# Phase_Voltages.net
KiCad netlist of a schematic drawn in Altium Designer
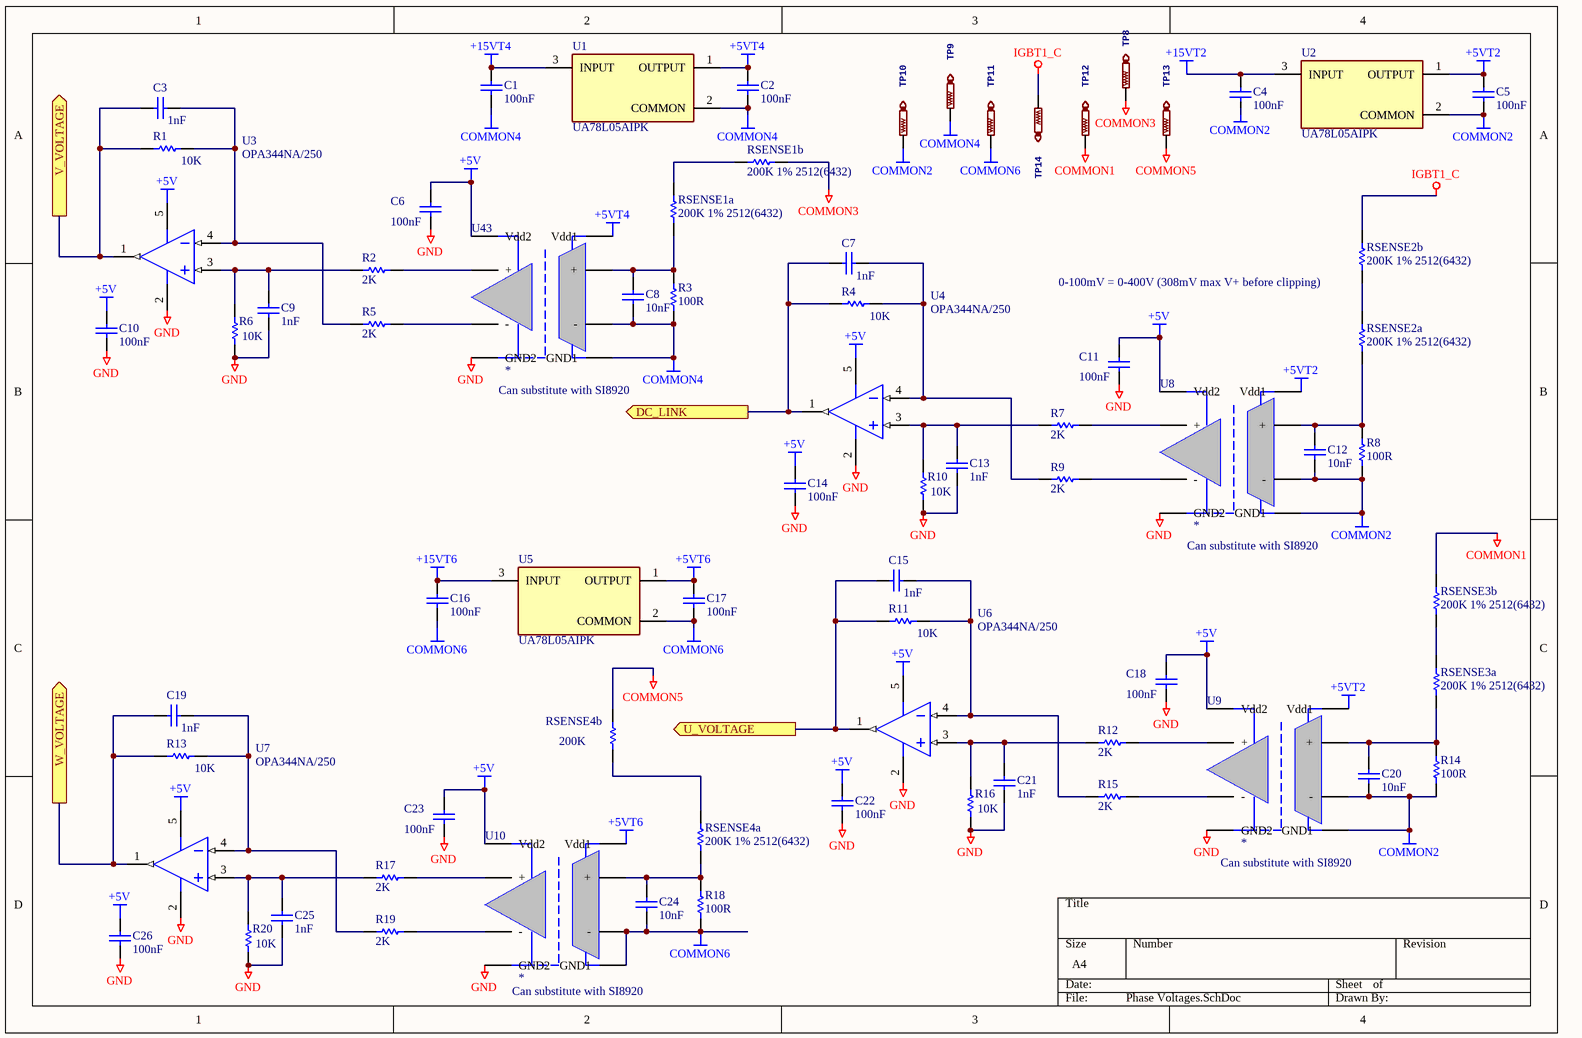
[diagram p0: Phase Voltages.SchDoc]

(export (version "E")
  (design (tool "Eeschema 10.0.6"))
  (components
    (comp (ref "C1")
      (value "100nF")
      (footprint "CAPC0805(2012)75_N")
      (description "CAP 100nF 25V -20% to +80% 0805 (2012 Metric) Thickness 0.75mm SMD")
      (fields (field (name "TOLERANCE") "-20% to +80%") (field (name "Comment") "CAP 100nF 25V 0805(2012)"))
      (libsource (lib "Altium Content Vault") (part "CMP-1036-04415-1"))
    )
    (comp (ref "C2")
      (value "100nF")
      (footprint "CAPC0805(2012)75_N")
      (description "CAP 100nF 25V -20% to +80% 0805 (2012 Metric) Thickness 0.75mm SMD")
      (fields (field (name "TOLERANCE") "-20% to +80%") (field (name "Comment") "CAP 100nF 25V 0805(2012)"))
      (libsource (lib "Altium Content Vault") (part "CMP-1036-04415-1"))
    )
    (comp (ref "C3")
      (value "1nF")
      (footprint "CAPC0805(2012)145_L")
      (description "CAP 1nF 16V ±5% 0805 (2012 Metric) Thickness 1.45mm SMD")
      (fields (field (name "TOLERANCE") "Â±5%") (field (name "Comment") "CAP 1nF 16V 0805(2012)"))
      (libsource (lib "Altium Content Vault") (part "CMP-1036-02957-1"))
    )
    (comp (ref "C4")
      (value "100nF")
      (footprint "CAPC0805(2012)75_N")
      (description "CAP 100nF 25V -20% to +80% 0805 (2012 Metric) Thickness 0.75mm SMD")
      (fields (field (name "TOLERANCE") "-20% to +80%") (field (name "Comment") "CAP 100nF 25V 0805(2012)"))
      (libsource (lib "Altium Content Vault") (part "CMP-1036-04415-1"))
    )
    (comp (ref "C5")
      (value "100nF")
      (footprint "CAPC0805(2012)75_N")
      (description "CAP 100nF 25V -20% to +80% 0805 (2012 Metric) Thickness 0.75mm SMD")
      (fields (field (name "TOLERANCE") "-20% to +80%") (field (name "Comment") "CAP 100nF 25V 0805(2012)"))
      (libsource (lib "Altium Content Vault") (part "CMP-1036-04415-1"))
    )
    (comp (ref "C6")
      (value "100nF")
      (footprint "CAPC0805(2012)75_N")
      (description "CAP 100nF 25V -20% to +80% 0805 (2012 Metric) Thickness 0.75mm SMD")
      (fields (field (name "TOLERANCE") "-20% to +80%") (field (name "Comment") "CAP 100nF 25V 0805(2012)"))
      (libsource (lib "Altium Content Vault") (part "CMP-1036-04415-1"))
    )
    (comp (ref "C7")
      (value "1nF")
      (footprint "CAPC0805(2012)145_L")
      (description "CAP 1nF 16V ±5% 0805 (2012 Metric) Thickness 1.45mm SMD")
      (fields (field (name "TOLERANCE") "Â±5%") (field (name "Comment") "CAP 1nF 16V 0805(2012)"))
      (libsource (lib "Altium Content Vault") (part "CMP-1036-02957-1"))
    )
    (comp (ref "C8")
      (value "10nF")
      (footprint "CAPC0805(2012)100_L")
      (description "CAP 10nF 25V ±5% 0805 (2012 Metric) Thickness 1mm SMD")
      (fields (field (name "TOLERANCE") "Â±5%") (field (name "Comment") "CAP 10nF 25V 0805(2012)"))
      (libsource (lib "Altium Content Vault") (part "CMP-1036-03829-1"))
    )
    (comp (ref "C9")
      (value "1nF")
      (footprint "CAPC0805(2012)145_L")
      (description "CAP 1nF 16V ±5% 0805 (2012 Metric) Thickness 1.45mm SMD")
      (fields (field (name "TOLERANCE") "Â±5%") (field (name "Comment") "CAP 1nF 16V 0805(2012)"))
      (libsource (lib "Altium Content Vault") (part "CMP-1036-02957-1"))
    )
    (comp (ref "C10")
      (value "100nF")
      (footprint "CAPC0805(2012)75_N")
      (description "CAP 100nF 25V -20% to +80% 0805 (2012 Metric) Thickness 0.75mm SMD")
      (fields (field (name "TOLERANCE") "-20% to +80%") (field (name "Comment") "CAP 100nF 25V 0805(2012)"))
      (libsource (lib "Altium Content Vault") (part "CMP-1036-04415-1"))
    )
    (comp (ref "C11")
      (value "100nF")
      (footprint "CAPC0805(2012)75_N")
      (description "CAP 100nF 25V -20% to +80% 0805 (2012 Metric) Thickness 0.75mm SMD")
      (fields (field (name "TOLERANCE") "-20% to +80%") (field (name "Comment") "CAP 100nF 25V 0805(2012)"))
      (libsource (lib "Altium Content Vault") (part "CMP-1036-04415-1"))
    )
    (comp (ref "C12")
      (value "10nF")
      (footprint "CAPC0805(2012)100_L")
      (description "CAP 10nF 25V ±5% 0805 (2012 Metric) Thickness 1mm SMD")
      (fields (field (name "TOLERANCE") "Â±5%") (field (name "Comment") "CAP 10nF 25V 0805(2012)"))
      (libsource (lib "Altium Content Vault") (part "CMP-1036-03829-1"))
    )
    (comp (ref "C13")
      (value "1nF")
      (footprint "CAPC0805(2012)145_L")
      (description "CAP 1nF 16V ±5% 0805 (2012 Metric) Thickness 1.45mm SMD")
      (fields (field (name "TOLERANCE") "Â±5%") (field (name "Comment") "CAP 1nF 16V 0805(2012)"))
      (libsource (lib "Altium Content Vault") (part "CMP-1036-02957-1"))
    )
    (comp (ref "C14")
      (value "100nF")
      (footprint "CAPC0805(2012)75_N")
      (description "CAP 100nF 25V -20% to +80% 0805 (2012 Metric) Thickness 0.75mm SMD")
      (fields (field (name "TOLERANCE") "-20% to +80%") (field (name "Comment") "CAP 100nF 25V 0805(2012)"))
      (libsource (lib "Altium Content Vault") (part "CMP-1036-04415-1"))
    )
    (comp (ref "C15")
      (value "1nF")
      (footprint "CAPC0805(2012)145_L")
      (description "CAP 1nF 16V ±5% 0805 (2012 Metric) Thickness 1.45mm SMD")
      (fields (field (name "TOLERANCE") "Â±5%") (field (name "Comment") "CAP 1nF 16V 0805(2012)"))
      (libsource (lib "Altium Content Vault") (part "CMP-1036-02957-1"))
    )
    (comp (ref "C16")
      (value "100nF")
      (footprint "CAPC0805(2012)75_N")
      (description "CAP 100nF 25V -20% to +80% 0805 (2012 Metric) Thickness 0.75mm SMD")
      (fields (field (name "TOLERANCE") "-20% to +80%") (field (name "Comment") "CAP 100nF 25V 0805(2012)"))
      (libsource (lib "Altium Content Vault") (part "CMP-1036-04415-1"))
    )
    (comp (ref "C17")
      (value "100nF")
      (footprint "CAPC0805(2012)75_N")
      (description "CAP 100nF 25V -20% to +80% 0805 (2012 Metric) Thickness 0.75mm SMD")
      (fields (field (name "TOLERANCE") "-20% to +80%") (field (name "Comment") "CAP 100nF 25V 0805(2012)"))
      (libsource (lib "Altium Content Vault") (part "CMP-1036-04415-1"))
    )
    (comp (ref "C18")
      (value "100nF")
      (footprint "CAPC0805(2012)75_N")
      (description "CAP 100nF 25V -20% to +80% 0805 (2012 Metric) Thickness 0.75mm SMD")
      (fields (field (name "TOLERANCE") "-20% to +80%") (field (name "Comment") "CAP 100nF 25V 0805(2012)"))
      (libsource (lib "Altium Content Vault") (part "CMP-1036-04415-1"))
    )
    (comp (ref "C19")
      (value "1nF")
      (footprint "CAPC0805(2012)145_L")
      (description "CAP 1nF 16V ±5% 0805 (2012 Metric) Thickness 1.45mm SMD")
      (fields (field (name "TOLERANCE") "Â±5%") (field (name "Comment") "CAP 1nF 16V 0805(2012)"))
      (libsource (lib "Altium Content Vault") (part "CMP-1036-02957-1"))
    )
    (comp (ref "C20")
      (value "10nF")
      (footprint "CAPC0805(2012)100_L")
      (description "CAP 10nF 25V ±5% 0805 (2012 Metric) Thickness 1mm SMD")
      (fields (field (name "TOLERANCE") "Â±5%") (field (name "Comment") "CAP 10nF 25V 0805(2012)"))
      (libsource (lib "Altium Content Vault") (part "CMP-1036-03829-1"))
    )
    (comp (ref "C21")
      (value "1nF")
      (footprint "CAPC0805(2012)145_L")
      (description "CAP 1nF 16V ±5% 0805 (2012 Metric) Thickness 1.45mm SMD")
      (fields (field (name "TOLERANCE") "Â±5%") (field (name "Comment") "CAP 1nF 16V 0805(2012)"))
      (libsource (lib "Altium Content Vault") (part "CMP-1036-02957-1"))
    )
    (comp (ref "C22")
      (value "100nF")
      (footprint "CAPC0805(2012)75_N")
      (description "CAP 100nF 25V -20% to +80% 0805 (2012 Metric) Thickness 0.75mm SMD")
      (fields (field (name "TOLERANCE") "-20% to +80%") (field (name "Comment") "CAP 100nF 25V 0805(2012)"))
      (libsource (lib "Altium Content Vault") (part "CMP-1036-04415-1"))
    )
    (comp (ref "C23")
      (value "100nF")
      (footprint "CAPC0805(2012)75_N")
      (description "CAP 100nF 25V -20% to +80% 0805 (2012 Metric) Thickness 0.75mm SMD")
      (fields (field (name "TOLERANCE") "-20% to +80%") (field (name "Comment") "CAP 100nF 25V 0805(2012)"))
      (libsource (lib "Altium Content Vault") (part "CMP-1036-04415-1"))
    )
    (comp (ref "C24")
      (value "10nF")
      (footprint "CAPC0805(2012)100_L")
      (description "CAP 10nF 25V ±5% 0805 (2012 Metric) Thickness 1mm SMD")
      (fields (field (name "TOLERANCE") "Â±5%") (field (name "Comment") "CAP 10nF 25V 0805(2012)"))
      (libsource (lib "Altium Content Vault") (part "CMP-1036-03829-1"))
    )
    (comp (ref "C25")
      (value "1nF")
      (footprint "CAPC0805(2012)145_L")
      (description "CAP 1nF 16V ±5% 0805 (2012 Metric) Thickness 1.45mm SMD")
      (fields (field (name "TOLERANCE") "Â±5%") (field (name "Comment") "CAP 1nF 16V 0805(2012)"))
      (libsource (lib "Altium Content Vault") (part "CMP-1036-02957-1"))
    )
    (comp (ref "C26")
      (value "100nF")
      (footprint "CAPC0805(2012)75_N")
      (description "CAP 100nF 25V -20% to +80% 0805 (2012 Metric) Thickness 0.75mm SMD")
      (fields (field (name "TOLERANCE") "-20% to +80%") (field (name "Comment") "CAP 100nF 25V 0805(2012)"))
      (libsource (lib "Altium Content Vault") (part "CMP-1036-04415-1"))
    )
    (comp (ref "R1")
      (value "10K")
      (footprint "RESC0805(2012)_M")
      (description "10K 0.125W 1% 0805 (2012 Metric)  SMD")
      (fields (field (name "TOLERANCE") "1 %") (field (name "POWER") "0.125 W"))
      (libsource (lib "Altium Content Vault") (part "CMP-1013-00623-1"))
    )
    (comp (ref "R2")
      (value "2K")
      (footprint "RESC0805(2012)_L")
      (description "2K 0.125W 1% 0805 (2012 Metric)  SMD")
      (fields (field (name "POWER") "0.125 W") (field (name "TOLERANCE") "1 %"))
      (libsource (lib "Altium Content Vault") (part "CMP-1013-00542-1"))
    )
    (comp (ref "R3")
      (value "100R")
      (footprint "RESC0805(2012)_L")
      (description "100R 0.125W 1% 0805 (2012 Metric)  SMD")
      (fields (field (name "POWER") "0.125 W") (field (name "TOLERANCE") "1 %"))
      (libsource (lib "Altium Content Vault") (part "CMP-1013-00397-1"))
    )
    (comp (ref "R4")
      (value "10K")
      (footprint "RESC0805(2012)_M")
      (description "10K 0.125W 1% 0805 (2012 Metric)  SMD")
      (fields (field (name "TOLERANCE") "1 %") (field (name "POWER") "0.125 W"))
      (libsource (lib "Altium Content Vault") (part "CMP-1013-00623-1"))
    )
    (comp (ref "R5")
      (value "2K")
      (footprint "RESC0805(2012)_L")
      (description "2K 0.125W 1% 0805 (2012 Metric)  SMD")
      (fields (field (name "POWER") "0.125 W") (field (name "TOLERANCE") "1 %"))
      (libsource (lib "Altium Content Vault") (part "CMP-1013-00542-1"))
    )
    (comp (ref "R6")
      (value "10K")
      (footprint "RESC0805(2012)_M")
      (description "10K 0.125W 1% 0805 (2012 Metric)  SMD")
      (fields (field (name "TOLERANCE") "1 %") (field (name "POWER") "0.125 W"))
      (libsource (lib "Altium Content Vault") (part "CMP-1013-00623-1"))
    )
    (comp (ref "R7")
      (value "2K")
      (footprint "RESC0805(2012)_L")
      (description "2K 0.125W 1% 0805 (2012 Metric)  SMD")
      (fields (field (name "POWER") "0.125 W") (field (name "TOLERANCE") "1 %"))
      (libsource (lib "Altium Content Vault") (part "CMP-1013-00542-1"))
    )
    (comp (ref "R8")
      (value "100R")
      (footprint "RESC0805(2012)_L")
      (description "100R 0.125W 1% 0805 (2012 Metric)  SMD")
      (fields (field (name "POWER") "0.125 W") (field (name "TOLERANCE") "1 %"))
      (libsource (lib "Altium Content Vault") (part "CMP-1013-00397-1"))
    )
    (comp (ref "R9")
      (value "2K")
      (footprint "RESC0805(2012)_L")
      (description "2K 0.125W 1% 0805 (2012 Metric)  SMD")
      (fields (field (name "POWER") "0.125 W") (field (name "TOLERANCE") "1 %"))
      (libsource (lib "Altium Content Vault") (part "CMP-1013-00542-1"))
    )
    (comp (ref "R10")
      (value "10K")
      (footprint "RESC0805(2012)_M")
      (description "10K 0.125W 1% 0805 (2012 Metric)  SMD")
      (fields (field (name "TOLERANCE") "1 %") (field (name "POWER") "0.125 W"))
      (libsource (lib "Altium Content Vault") (part "CMP-1013-00623-1"))
    )
    (comp (ref "R11")
      (value "10K")
      (footprint "RESC0805(2012)_M")
      (description "10K 0.125W 1% 0805 (2012 Metric)  SMD")
      (fields (field (name "TOLERANCE") "1 %") (field (name "POWER") "0.125 W"))
      (libsource (lib "Altium Content Vault") (part "CMP-1013-00623-1"))
    )
    (comp (ref "R12")
      (value "2K")
      (footprint "RESC0805(2012)_L")
      (description "2K 0.125W 1% 0805 (2012 Metric)  SMD")
      (fields (field (name "POWER") "0.125 W") (field (name "TOLERANCE") "1 %"))
      (libsource (lib "Altium Content Vault") (part "CMP-1013-00542-1"))
    )
    (comp (ref "R13")
      (value "10K")
      (footprint "RESC0805(2012)_M")
      (description "10K 0.125W 1% 0805 (2012 Metric)  SMD")
      (fields (field (name "TOLERANCE") "1 %") (field (name "POWER") "0.125 W"))
      (libsource (lib "Altium Content Vault") (part "CMP-1013-00623-1"))
    )
    (comp (ref "R14")
      (value "100R")
      (footprint "RESC0805(2012)_L")
      (description "100R 0.125W 1% 0805 (2012 Metric)  SMD")
      (fields (field (name "POWER") "0.125 W") (field (name "TOLERANCE") "1 %"))
      (libsource (lib "Altium Content Vault") (part "CMP-1013-00397-1"))
    )
    (comp (ref "R15")
      (value "2K")
      (footprint "RESC0805(2012)_L")
      (description "2K 0.125W 1% 0805 (2012 Metric)  SMD")
      (fields (field (name "POWER") "0.125 W") (field (name "TOLERANCE") "1 %"))
      (libsource (lib "Altium Content Vault") (part "CMP-1013-00542-1"))
    )
    (comp (ref "R16")
      (value "10K")
      (footprint "RESC0805(2012)_M")
      (description "10K 0.125W 1% 0805 (2012 Metric)  SMD")
      (fields (field (name "TOLERANCE") "1 %") (field (name "POWER") "0.125 W"))
      (libsource (lib "Altium Content Vault") (part "CMP-1013-00623-1"))
    )
    (comp (ref "R17")
      (value "2K")
      (footprint "RESC0805(2012)_L")
      (description "2K 0.125W 1% 0805 (2012 Metric)  SMD")
      (fields (field (name "POWER") "0.125 W") (field (name "TOLERANCE") "1 %"))
      (libsource (lib "Altium Content Vault") (part "CMP-1013-00542-1"))
    )
    (comp (ref "R18")
      (value "100R")
      (footprint "RESC0805(2012)_L")
      (description "100R 0.125W 1% 0805 (2012 Metric)  SMD")
      (fields (field (name "POWER") "0.125 W") (field (name "TOLERANCE") "1 %"))
      (libsource (lib "Altium Content Vault") (part "CMP-1013-00397-1"))
    )
    (comp (ref "R19")
      (value "2K")
      (footprint "RESC0805(2012)_L")
      (description "2K 0.125W 1% 0805 (2012 Metric)  SMD")
      (fields (field (name "POWER") "0.125 W") (field (name "TOLERANCE") "1 %"))
      (libsource (lib "Altium Content Vault") (part "CMP-1013-00542-1"))
    )
    (comp (ref "R20")
      (value "10K")
      (footprint "RESC0805(2012)_M")
      (description "10K 0.125W 1% 0805 (2012 Metric)  SMD")
      (fields (field (name "TOLERANCE") "1 %") (field (name "POWER") "0.125 W"))
      (libsource (lib "Altium Content Vault") (part "CMP-1013-00623-1"))
    )
    (comp (ref "RSENSE1a")
      (value "200K 1% 2512(6432)")
      (footprint "RESC2512(6432)_M")
      (description "200K 1W 1% 2512 (6432 Metric)  SMD")
      (fields (field (name "TOLERANCE") "1 %") (field (name "POWER") "1 W"))
      (libsource (lib "Altium Content Vault") (part "RES"))
    )
    (comp (ref "RSENSE1b")
      (value "200K 1% 2512(6432)")
      (footprint "RESC2512(6432)_M")
      (description "200K 1W 1% 2512 (6432 Metric)  SMD")
      (fields (field (name "TOLERANCE") "1 %") (field (name "POWER") "1 W"))
      (libsource (lib "Altium Content Vault") (part "RES"))
    )
    (comp (ref "RSENSE2a")
      (value "200K 1% 2512(6432)")
      (footprint "RESC2512(6432)_M")
      (description "200K 1W 1% 2512 (6432 Metric)  SMD")
      (fields (field (name "TOLERANCE") "1 %") (field (name "POWER") "1 W"))
      (libsource (lib "Altium Content Vault") (part "RES"))
    )
    (comp (ref "RSENSE2b")
      (value "200K 1% 2512(6432)")
      (footprint "RESC2512(6432)_M")
      (description "200K 1W 1% 2512 (6432 Metric)  SMD")
      (fields (field (name "TOLERANCE") "1 %") (field (name "POWER") "1 W"))
      (libsource (lib "Altium Content Vault") (part "RES"))
    )
    (comp (ref "RSENSE3a")
      (value "200K 1% 2512(6432)")
      (footprint "RESC2512(6432)_M")
      (description "200K 1W 1% 2512 (6432 Metric)  SMD")
      (fields (field (name "TOLERANCE") "1 %") (field (name "POWER") "1 W"))
      (libsource (lib "Altium Content Vault") (part "RES"))
    )
    (comp (ref "RSENSE3b")
      (value "200K 1% 2512(6432)")
      (footprint "RESC2512(6432)_M")
      (description "200K 1W 1% 2512 (6432 Metric)  SMD")
      (fields (field (name "TOLERANCE") "1 %") (field (name "POWER") "1 W"))
      (libsource (lib "Altium Content Vault") (part "RES"))
    )
    (comp (ref "RSENSE4a")
      (value "200K 1% 2512(6432)")
      (footprint "RESC2512(6432)_M")
      (description "200K 1W 1% 2512 (6432 Metric)  SMD")
      (fields (field (name "TOLERANCE") "1 %") (field (name "POWER") "1 W"))
      (libsource (lib "Altium Content Vault") (part "CMP-1018-00768-1"))
    )
    (comp (ref "RSENSE4b")
      (value "200K")
      (footprint "RESC2512(6432)_M")
      (description "200K 1W 1% 2512 (6432 Metric)  SMD")
      (fields (field (name "TOLERANCE") "1 %") (field (name "POWER") "1 W"))
      (libsource (lib "Altium Content Vault") (part "CMP-1018-00768-1"))
    )
    (comp (ref "TP8")
      (value "PTR1PAD1-13")
      (footprint "P1-13")
      (description "TEST PIN")
      (libsource (lib "testpad") (part "PTR1PAD1-13"))
    )
    (comp (ref "TP9")
      (value "PTR1PAD1-13")
      (footprint "P1-13")
      (description "TEST PIN")
      (libsource (lib "testpad") (part "PTR1PAD1-13"))
    )
    (comp (ref "TP10")
      (value "PTR1PAD1-13")
      (footprint "P1-13")
      (description "TEST PIN")
      (libsource (lib "testpad") (part "PTR1PAD1-13"))
    )
    (comp (ref "TP11")
      (value "PTR1PAD1-13")
      (footprint "P1-13")
      (description "TEST PIN")
      (libsource (lib "testpad") (part "PTR1PAD1-13"))
    )
    (comp (ref "TP12")
      (value "PTR1PAD1-13")
      (footprint "P1-13")
      (description "TEST PIN")
      (libsource (lib "testpad") (part "PTR1PAD1-13"))
    )
    (comp (ref "TP13")
      (value "PTR1PAD1-13")
      (footprint "P1-13")
      (description "TEST PIN")
      (libsource (lib "testpad") (part "PTR1PAD1-13"))
    )
    (comp (ref "TP14")
      (value "PTR1PAD1-13")
      (footprint "P1-13")
      (description "TEST PIN")
      (libsource (lib "") (part "PTR1PAD1-13_1"))
    )
    (comp (ref "U1")
      (value "UA78L05AIPK")
      (footprint "FP-PK0003A-MFG")
      (description "IC REG LINEAR 5V 100MA SOT89-3")
      (fields
        (field (name "MANUFACTURER") "Texas Instruments")
        (field (name "OCTOPART") "https://octopart.com/ua78l05aipk-texas+instruments-525592")
      )
      (libsource (lib "Altium Content Vault") (part "58e5423477dba73b0af001d1dc47a63"))
    )
    (comp (ref "U2")
      (value "UA78L05AIPK")
      (footprint "FP-PK0003A-MFG")
      (description "IC REG LINEAR 5V 100MA SOT89-3")
      (fields
        (field (name "MANUFACTURER") "Texas Instruments")
        (field (name "OCTOPART") "https://octopart.com/ua78l05aipk-texas+instruments-525592")
      )
      (libsource (lib "Altium Content Vault") (part "58e5423477dba73b0af001d1dc47a63"))
    )
    (comp (ref "U3")
      (value "OPA344NA/250")
      (footprint "DBV0005A_L")
      (fields (field (name "MANUFACTURER") "Texas Instruments"))
      (libsource (lib "Altium Content Vault") (part "CMP-0272-00879-3"))
    )
    (comp (ref "U4")
      (value "OPA344NA/250")
      (footprint "DBV0005A_L")
      (fields (field (name "MANUFACTURER") "Texas Instruments"))
      (libsource (lib "Altium Content Vault") (part "CMP-0272-00879-3"))
    )
    (comp (ref "U5")
      (value "UA78L05AIPK")
      (footprint "FP-PK0003A-MFG")
      (description "IC REG LINEAR 5V 100MA SOT89-3")
      (fields
        (field (name "MANUFACTURER") "Texas Instruments")
        (field (name "OCTOPART") "https://octopart.com/ua78l05aipk-texas+instruments-525592")
      )
      (libsource (lib "Altium Content Vault") (part "58e5423477dba73b0af001d1dc47a63"))
    )
    (comp (ref "U6")
      (value "OPA344NA/250")
      (footprint "DBV0005A_L")
      (fields (field (name "MANUFACTURER") "Texas Instruments"))
      (libsource (lib "Altium Content Vault") (part "CMP-0272-00879-3"))
    )
    (comp (ref "U7")
      (value "OPA344NA/250")
      (footprint "DBV0005A_L")
      (fields (field (name "MANUFACTURER") "Texas Instruments"))
      (libsource (lib "Altium Content Vault") (part "CMP-0272-00879-3"))
    )
    (comp (ref "U8")
      (value "*")
      (footprint "SOP8")
      (libsource (lib "Gatedrive Power") (part "HCPL-7800-300E"))
    )
    (comp (ref "U9")
      (value "*")
      (footprint "SOP8")
      (libsource (lib "Gatedrive Power") (part "HCPL-7800-300E"))
    )
    (comp (ref "U10")
      (value "*")
      (footprint "SOP8")
      (libsource (lib "Gatedrive Power") (part "HCPL-7800-300E"))
    )
    (comp (ref "U43")
      (value "*")
      (footprint "SOP8")
      (libsource (lib "Gatedrive Power") (part "HCPL-7800-300E"))
    )
  )
  (nets
    (net (code "1") (name "+5V") (class "Default")
      (node (ref "C10") (pin "1") (pinfunction "1_1") (pintype "passive"))
      (node (ref "C11") (pin "1") (pinfunction "1_1") (pintype "passive"))
      (node (ref "C14") (pin "1") (pinfunction "1_1") (pintype "passive"))
      (node (ref "C18") (pin "1") (pinfunction "1_1") (pintype "passive"))
      (node (ref "C22") (pin "1") (pinfunction "1_1") (pintype "passive"))
      (node (ref "C23") (pin "1") (pinfunction "1_1") (pintype "passive"))
      (node (ref "C26") (pin "1") (pinfunction "1_1") (pintype "passive"))
      (node (ref "C6") (pin "1") (pinfunction "1_1") (pintype "passive"))
      (node (ref "U10") (pin "8") (pinfunction "Vdd2_8") (pintype "passive"))
      (node (ref "U3") (pin "5") (pinfunction "V+_5") (pintype "power_in"))
      (node (ref "U4") (pin "5") (pinfunction "V+_5") (pintype "power_in"))
      (node (ref "U43") (pin "8") (pinfunction "Vdd2_8") (pintype "passive"))
      (node (ref "U6") (pin "5") (pinfunction "V+_5") (pintype "power_in"))
      (node (ref "U7") (pin "5") (pinfunction "V+_5") (pintype "power_in"))
      (node (ref "U8") (pin "8") (pinfunction "Vdd2_8") (pintype "passive"))
      (node (ref "U9") (pin "8") (pinfunction "Vdd2_8") (pintype "passive"))
    )
    (net (code "2") (name "+5VT2") (class "Default")
      (node (ref "C5") (pin "2") (pinfunction "2_2") (pintype "passive"))
      (node (ref "U2") (pin "1") (pinfunction "OUTPUT_1") (pintype "power_in"))
      (node (ref "U8") (pin "1") (pinfunction "Vdd1_1") (pintype "passive"))
      (node (ref "U9") (pin "1") (pinfunction "Vdd1_1") (pintype "passive"))
    )
    (net (code "3") (name "+5VT4") (class "Default")
      (node (ref "C2") (pin "2") (pinfunction "2_2") (pintype "passive"))
      (node (ref "U1") (pin "1") (pinfunction "OUTPUT_1") (pintype "power_in"))
      (node (ref "U43") (pin "1") (pinfunction "Vdd1_1") (pintype "passive"))
    )
    (net (code "4") (name "+5VT6") (class "Default")
      (node (ref "C17") (pin "2") (pinfunction "2_2") (pintype "passive"))
      (node (ref "U10") (pin "1") (pinfunction "Vdd1_1") (pintype "passive"))
      (node (ref "U5") (pin "1") (pinfunction "OUTPUT_1") (pintype "power_in"))
    )
    (net (code "5") (name "+15VT2") (class "Default")
      (node (ref "C4") (pin "2") (pinfunction "2_2") (pintype "passive"))
      (node (ref "U2") (pin "3") (pinfunction "INPUT_3") (pintype "power_in"))
    )
    (net (code "6") (name "+15VT4") (class "Default")
      (node (ref "C1") (pin "2") (pinfunction "2_2") (pintype "passive"))
      (node (ref "U1") (pin "3") (pinfunction "INPUT_3") (pintype "power_in"))
    )
    (net (code "7") (name "+15VT6") (class "Default")
      (node (ref "C16") (pin "2") (pinfunction "2_2") (pintype "passive"))
      (node (ref "U5") (pin "3") (pinfunction "INPUT_3") (pintype "power_in"))
    )
    (net (code "8") (name "/DC_LINK") (class "Default")
      (node (ref "C7") (pin "1") (pinfunction "1_1") (pintype "passive"))
      (node (ref "R4") (pin "1") (pinfunction "1_1") (pintype "passive"))
      (node (ref "U4") (pin "1") (pinfunction "OUT_1") (pintype "output"))
    )
    (net (code "9") (name "/U_VOLTAGE") (class "Default")
      (node (ref "C15") (pin "1") (pinfunction "1_1") (pintype "passive"))
      (node (ref "R11") (pin "1") (pinfunction "1_1") (pintype "passive"))
      (node (ref "U6") (pin "1") (pinfunction "OUT_1") (pintype "output"))
    )
    (net (code "10") (name "/V_VOLTAGE") (class "Default")
      (node (ref "C3") (pin "1") (pinfunction "1_1") (pintype "passive"))
      (node (ref "R1") (pin "1") (pinfunction "1_1") (pintype "passive"))
      (node (ref "U3") (pin "1") (pinfunction "OUT_1") (pintype "output"))
    )
    (net (code "11") (name "/W_VOLTAGE") (class "Default")
      (node (ref "C19") (pin "1") (pinfunction "1_1") (pintype "passive"))
      (node (ref "R13") (pin "1") (pinfunction "1_1") (pintype "passive"))
      (node (ref "U7") (pin "1") (pinfunction "OUT_1") (pintype "output"))
    )
    (net (code "12") (name "COMMON1") (class "Default")
      (node (ref "RSENSE3b") (pin "2") (pinfunction "2_2") (pintype "passive"))
      (node (ref "TP12") (pin "TP") (pinfunction "TP_TP") (pintype "passive"))
    )
    (net (code "13") (name "COMMON2") (class "Default")
      (node (ref "C12") (pin "1") (pinfunction "1_1") (pintype "passive"))
      (node (ref "C20") (pin "1") (pinfunction "1_1") (pintype "passive"))
      (node (ref "C4") (pin "1") (pinfunction "1_1") (pintype "passive"))
      (node (ref "C5") (pin "1") (pinfunction "1_1") (pintype "passive"))
      (node (ref "R14") (pin "2") (pinfunction "2_2") (pintype "passive"))
      (node (ref "R8") (pin "2") (pinfunction "2_2") (pintype "passive"))
      (node (ref "TP10") (pin "TP") (pinfunction "TP_TP") (pintype "passive"))
      (node (ref "U2") (pin "2") (pinfunction "COMMON_2") (pintype "passive"))
      (node (ref "U8") (pin "3") (pinfunction "-_3") (pintype "passive"))
      (node (ref "U8") (pin "4") (pinfunction "GND1_4") (pintype "passive"))
      (node (ref "U9") (pin "3") (pinfunction "-_3") (pintype "passive"))
      (node (ref "U9") (pin "4") (pinfunction "GND1_4") (pintype "passive"))
    )
    (net (code "14") (name "COMMON3") (class "Default")
      (node (ref "RSENSE1b") (pin "1") (pinfunction "1_1") (pintype "passive"))
      (node (ref "TP8") (pin "TP") (pinfunction "TP_TP") (pintype "passive"))
    )
    (net (code "15") (name "COMMON4") (class "Default")
      (node (ref "C1") (pin "1") (pinfunction "1_1") (pintype "passive"))
      (node (ref "C2") (pin "1") (pinfunction "1_1") (pintype "passive"))
      (node (ref "C8") (pin "1") (pinfunction "1_1") (pintype "passive"))
      (node (ref "R3") (pin "2") (pinfunction "2_2") (pintype "passive"))
      (node (ref "TP9") (pin "TP") (pinfunction "TP_TP") (pintype "passive"))
      (node (ref "U1") (pin "2") (pinfunction "COMMON_2") (pintype "passive"))
      (node (ref "U43") (pin "3") (pinfunction "-_3") (pintype "passive"))
      (node (ref "U43") (pin "4") (pinfunction "GND1_4") (pintype "passive"))
    )
    (net (code "16") (name "COMMON5") (class "Default")
      (node (ref "RSENSE4b") (pin "2") (pinfunction "2_2") (pintype "passive"))
      (node (ref "TP13") (pin "TP") (pinfunction "TP_TP") (pintype "passive"))
    )
    (net (code "17") (name "COMMON6") (class "Default")
      (node (ref "C16") (pin "1") (pinfunction "1_1") (pintype "passive"))
      (node (ref "C17") (pin "1") (pinfunction "1_1") (pintype "passive"))
      (node (ref "C24") (pin "1") (pinfunction "1_1") (pintype "passive"))
      (node (ref "R18") (pin "2") (pinfunction "2_2") (pintype "passive"))
      (node (ref "TP11") (pin "TP") (pinfunction "TP_TP") (pintype "passive"))
      (node (ref "U10") (pin "3") (pinfunction "-_3") (pintype "passive"))
      (node (ref "U10") (pin "4") (pinfunction "GND1_4") (pintype "passive"))
      (node (ref "U5") (pin "2") (pinfunction "COMMON_2") (pintype "passive"))
    )
    (net (code "18") (name "GND") (class "Default")
      (node (ref "C10") (pin "2") (pinfunction "2_2") (pintype "passive"))
      (node (ref "C11") (pin "2") (pinfunction "2_2") (pintype "passive"))
      (node (ref "C13") (pin "1") (pinfunction "1_1") (pintype "passive"))
      (node (ref "C14") (pin "2") (pinfunction "2_2") (pintype "passive"))
      (node (ref "C18") (pin "2") (pinfunction "2_2") (pintype "passive"))
      (node (ref "C21") (pin "1") (pinfunction "1_1") (pintype "passive"))
      (node (ref "C22") (pin "2") (pinfunction "2_2") (pintype "passive"))
      (node (ref "C23") (pin "2") (pinfunction "2_2") (pintype "passive"))
      (node (ref "C25") (pin "1") (pinfunction "1_1") (pintype "passive"))
      (node (ref "C26") (pin "2") (pinfunction "2_2") (pintype "passive"))
      (node (ref "C6") (pin "2") (pinfunction "2_2") (pintype "passive"))
      (node (ref "C9") (pin "1") (pinfunction "1_1") (pintype "passive"))
      (node (ref "R10") (pin "1") (pinfunction "1_1") (pintype "passive"))
      (node (ref "R16") (pin "1") (pinfunction "1_1") (pintype "passive"))
      (node (ref "R20") (pin "1") (pinfunction "1_1") (pintype "passive"))
      (node (ref "R6") (pin "1") (pinfunction "1_1") (pintype "passive"))
      (node (ref "U10") (pin "5") (pinfunction "GND2_5") (pintype "passive"))
      (node (ref "U3") (pin "2") (pinfunction "V-_2") (pintype "power_in"))
      (node (ref "U4") (pin "2") (pinfunction "V-_2") (pintype "power_in"))
      (node (ref "U43") (pin "5") (pinfunction "GND2_5") (pintype "passive"))
      (node (ref "U6") (pin "2") (pinfunction "V-_2") (pintype "power_in"))
      (node (ref "U7") (pin "2") (pinfunction "V-_2") (pintype "power_in"))
      (node (ref "U8") (pin "5") (pinfunction "GND2_5") (pintype "passive"))
      (node (ref "U9") (pin "5") (pinfunction "GND2_5") (pintype "passive"))
    )
    (net (code "19") (name "IGBT1_C") (class "Default")
      (node (ref "RSENSE2b") (pin "2") (pinfunction "2_2") (pintype "passive"))
      (node (ref "TP14") (pin "TP") (pinfunction "TP_TP") (pintype "passive"))
    )
    (net (code "20") (name "Net-(C8-Pad2)") (class "Default")
      (node (ref "C8") (pin "2") (pinfunction "2_2") (pintype "passive"))
      (node (ref "R3") (pin "1") (pinfunction "1_1") (pintype "passive"))
      (node (ref "RSENSE1a") (pin "1") (pinfunction "1_1") (pintype "passive"))
      (node (ref "U43") (pin "2") (pinfunction "+_2") (pintype "passive"))
    )
    (net (code "21") (name "Net-(C12-Pad2)") (class "Default")
      (node (ref "C12") (pin "2") (pinfunction "2_2") (pintype "passive"))
      (node (ref "R8") (pin "1") (pinfunction "1_1") (pintype "passive"))
      (node (ref "RSENSE2a") (pin "1") (pinfunction "1_1") (pintype "passive"))
      (node (ref "U8") (pin "2") (pinfunction "+_2") (pintype "passive"))
    )
    (net (code "22") (name "Net-(C20-Pad2)") (class "Default")
      (node (ref "C20") (pin "2") (pinfunction "2_2") (pintype "passive"))
      (node (ref "R14") (pin "1") (pinfunction "1_1") (pintype "passive"))
      (node (ref "RSENSE3a") (pin "1") (pinfunction "1_1") (pintype "passive"))
      (node (ref "U9") (pin "2") (pinfunction "+_2") (pintype "passive"))
    )
    (net (code "23") (name "Net-(C24-Pad2)") (class "Default")
      (node (ref "C24") (pin "2") (pinfunction "2_2") (pintype "passive"))
      (node (ref "R18") (pin "1") (pinfunction "1_1") (pintype "passive"))
      (node (ref "RSENSE4a") (pin "1") (pinfunction "1_1") (pintype "passive"))
      (node (ref "U10") (pin "2") (pinfunction "+_2") (pintype "passive"))
    )
    (net (code "24") (name "Net-(R2-Pad1)") (class "Default")
      (node (ref "R2") (pin "1") (pinfunction "1_1") (pintype "passive"))
      (node (ref "U43") (pin "7") (pinfunction "+_7") (pintype "passive"))
    )
    (net (code "25") (name "Net-(R5-Pad1)") (class "Default")
      (node (ref "R5") (pin "1") (pinfunction "1_1") (pintype "passive"))
      (node (ref "U43") (pin "6") (pinfunction "-_6") (pintype "passive"))
    )
    (net (code "26") (name "Net-(R7-Pad1)") (class "Default")
      (node (ref "R7") (pin "1") (pinfunction "1_1") (pintype "passive"))
      (node (ref "U8") (pin "7") (pinfunction "+_7") (pintype "passive"))
    )
    (net (code "27") (name "Net-(R9-Pad1)") (class "Default")
      (node (ref "R9") (pin "1") (pinfunction "1_1") (pintype "passive"))
      (node (ref "U8") (pin "6") (pinfunction "-_6") (pintype "passive"))
    )
    (net (code "28") (name "Net-(R12-Pad1)") (class "Default")
      (node (ref "R12") (pin "1") (pinfunction "1_1") (pintype "passive"))
      (node (ref "U9") (pin "7") (pinfunction "+_7") (pintype "passive"))
    )
    (net (code "29") (name "Net-(R15-Pad1)") (class "Default")
      (node (ref "R15") (pin "1") (pinfunction "1_1") (pintype "passive"))
      (node (ref "U9") (pin "6") (pinfunction "-_6") (pintype "passive"))
    )
    (net (code "30") (name "Net-(R17-Pad1)") (class "Default")
      (node (ref "R17") (pin "1") (pinfunction "1_1") (pintype "passive"))
      (node (ref "U10") (pin "7") (pinfunction "+_7") (pintype "passive"))
    )
    (net (code "31") (name "Net-(R19-Pad1)") (class "Default")
      (node (ref "R19") (pin "1") (pinfunction "1_1") (pintype "passive"))
      (node (ref "U10") (pin "6") (pinfunction "-_6") (pintype "passive"))
    )
    (net (code "32") (name "Net-(RSENSE1a-Pad2)") (class "Default")
      (node (ref "RSENSE1a") (pin "2") (pinfunction "2_2") (pintype "passive"))
      (node (ref "RSENSE1b") (pin "2") (pinfunction "2_2") (pintype "passive"))
    )
    (net (code "33") (name "Net-(RSENSE2a-Pad2)") (class "Default")
      (node (ref "RSENSE2a") (pin "2") (pinfunction "2_2") (pintype "passive"))
      (node (ref "RSENSE2b") (pin "1") (pinfunction "1_1") (pintype "passive"))
    )
    (net (code "34") (name "Net-(RSENSE3a-Pad2)") (class "Default")
      (node (ref "RSENSE3a") (pin "2") (pinfunction "2_2") (pintype "passive"))
      (node (ref "RSENSE3b") (pin "1") (pinfunction "1_1") (pintype "passive"))
    )
    (net (code "35") (name "Net-(RSENSE4a-Pad2)") (class "Default")
      (node (ref "RSENSE4a") (pin "2") (pinfunction "2_2") (pintype "passive"))
      (node (ref "RSENSE4b") (pin "1") (pinfunction "1_1") (pintype "passive"))
    )
    (net (code "36") (name "Net-(U3-IN+)") (class "Default")
      (node (ref "C9") (pin "2") (pinfunction "2_2") (pintype "passive"))
      (node (ref "R2") (pin "2") (pinfunction "2_2") (pintype "passive"))
      (node (ref "R6") (pin "2") (pinfunction "2_2") (pintype "passive"))
      (node (ref "U3") (pin "3") (pinfunction "IN+_3") (pintype "input"))
    )
    (net (code "37") (name "Net-(U3-IN-)") (class "Default")
      (node (ref "C3") (pin "2") (pinfunction "2_2") (pintype "passive"))
      (node (ref "R1") (pin "2") (pinfunction "2_2") (pintype "passive"))
      (node (ref "R5") (pin "2") (pinfunction "2_2") (pintype "passive"))
      (node (ref "U3") (pin "4") (pinfunction "IN-_4") (pintype "input"))
    )
    (net (code "38") (name "Net-(U4-IN+)") (class "Default")
      (node (ref "C13") (pin "2") (pinfunction "2_2") (pintype "passive"))
      (node (ref "R10") (pin "2") (pinfunction "2_2") (pintype "passive"))
      (node (ref "R7") (pin "2") (pinfunction "2_2") (pintype "passive"))
      (node (ref "U4") (pin "3") (pinfunction "IN+_3") (pintype "input"))
    )
    (net (code "39") (name "Net-(U4-IN-)") (class "Default")
      (node (ref "C7") (pin "2") (pinfunction "2_2") (pintype "passive"))
      (node (ref "R4") (pin "2") (pinfunction "2_2") (pintype "passive"))
      (node (ref "R9") (pin "2") (pinfunction "2_2") (pintype "passive"))
      (node (ref "U4") (pin "4") (pinfunction "IN-_4") (pintype "input"))
    )
    (net (code "40") (name "Net-(U6-IN+)") (class "Default")
      (node (ref "C21") (pin "2") (pinfunction "2_2") (pintype "passive"))
      (node (ref "R12") (pin "2") (pinfunction "2_2") (pintype "passive"))
      (node (ref "R16") (pin "2") (pinfunction "2_2") (pintype "passive"))
      (node (ref "U6") (pin "3") (pinfunction "IN+_3") (pintype "input"))
    )
    (net (code "41") (name "Net-(U6-IN-)") (class "Default")
      (node (ref "C15") (pin "2") (pinfunction "2_2") (pintype "passive"))
      (node (ref "R11") (pin "2") (pinfunction "2_2") (pintype "passive"))
      (node (ref "R15") (pin "2") (pinfunction "2_2") (pintype "passive"))
      (node (ref "U6") (pin "4") (pinfunction "IN-_4") (pintype "input"))
    )
    (net (code "42") (name "Net-(U7-IN+)") (class "Default")
      (node (ref "C25") (pin "2") (pinfunction "2_2") (pintype "passive"))
      (node (ref "R17") (pin "2") (pinfunction "2_2") (pintype "passive"))
      (node (ref "R20") (pin "2") (pinfunction "2_2") (pintype "passive"))
      (node (ref "U7") (pin "3") (pinfunction "IN+_3") (pintype "input"))
    )
    (net (code "43") (name "Net-(U7-IN-)") (class "Default")
      (node (ref "C19") (pin "2") (pinfunction "2_2") (pintype "passive"))
      (node (ref "R13") (pin "2") (pinfunction "2_2") (pintype "passive"))
      (node (ref "R19") (pin "2") (pinfunction "2_2") (pintype "passive"))
      (node (ref "U7") (pin "4") (pinfunction "IN-_4") (pintype "input"))
    )
  )
)
